# ltc2344-16.net
KiCad netlist of a schematic drawn in EAGLE
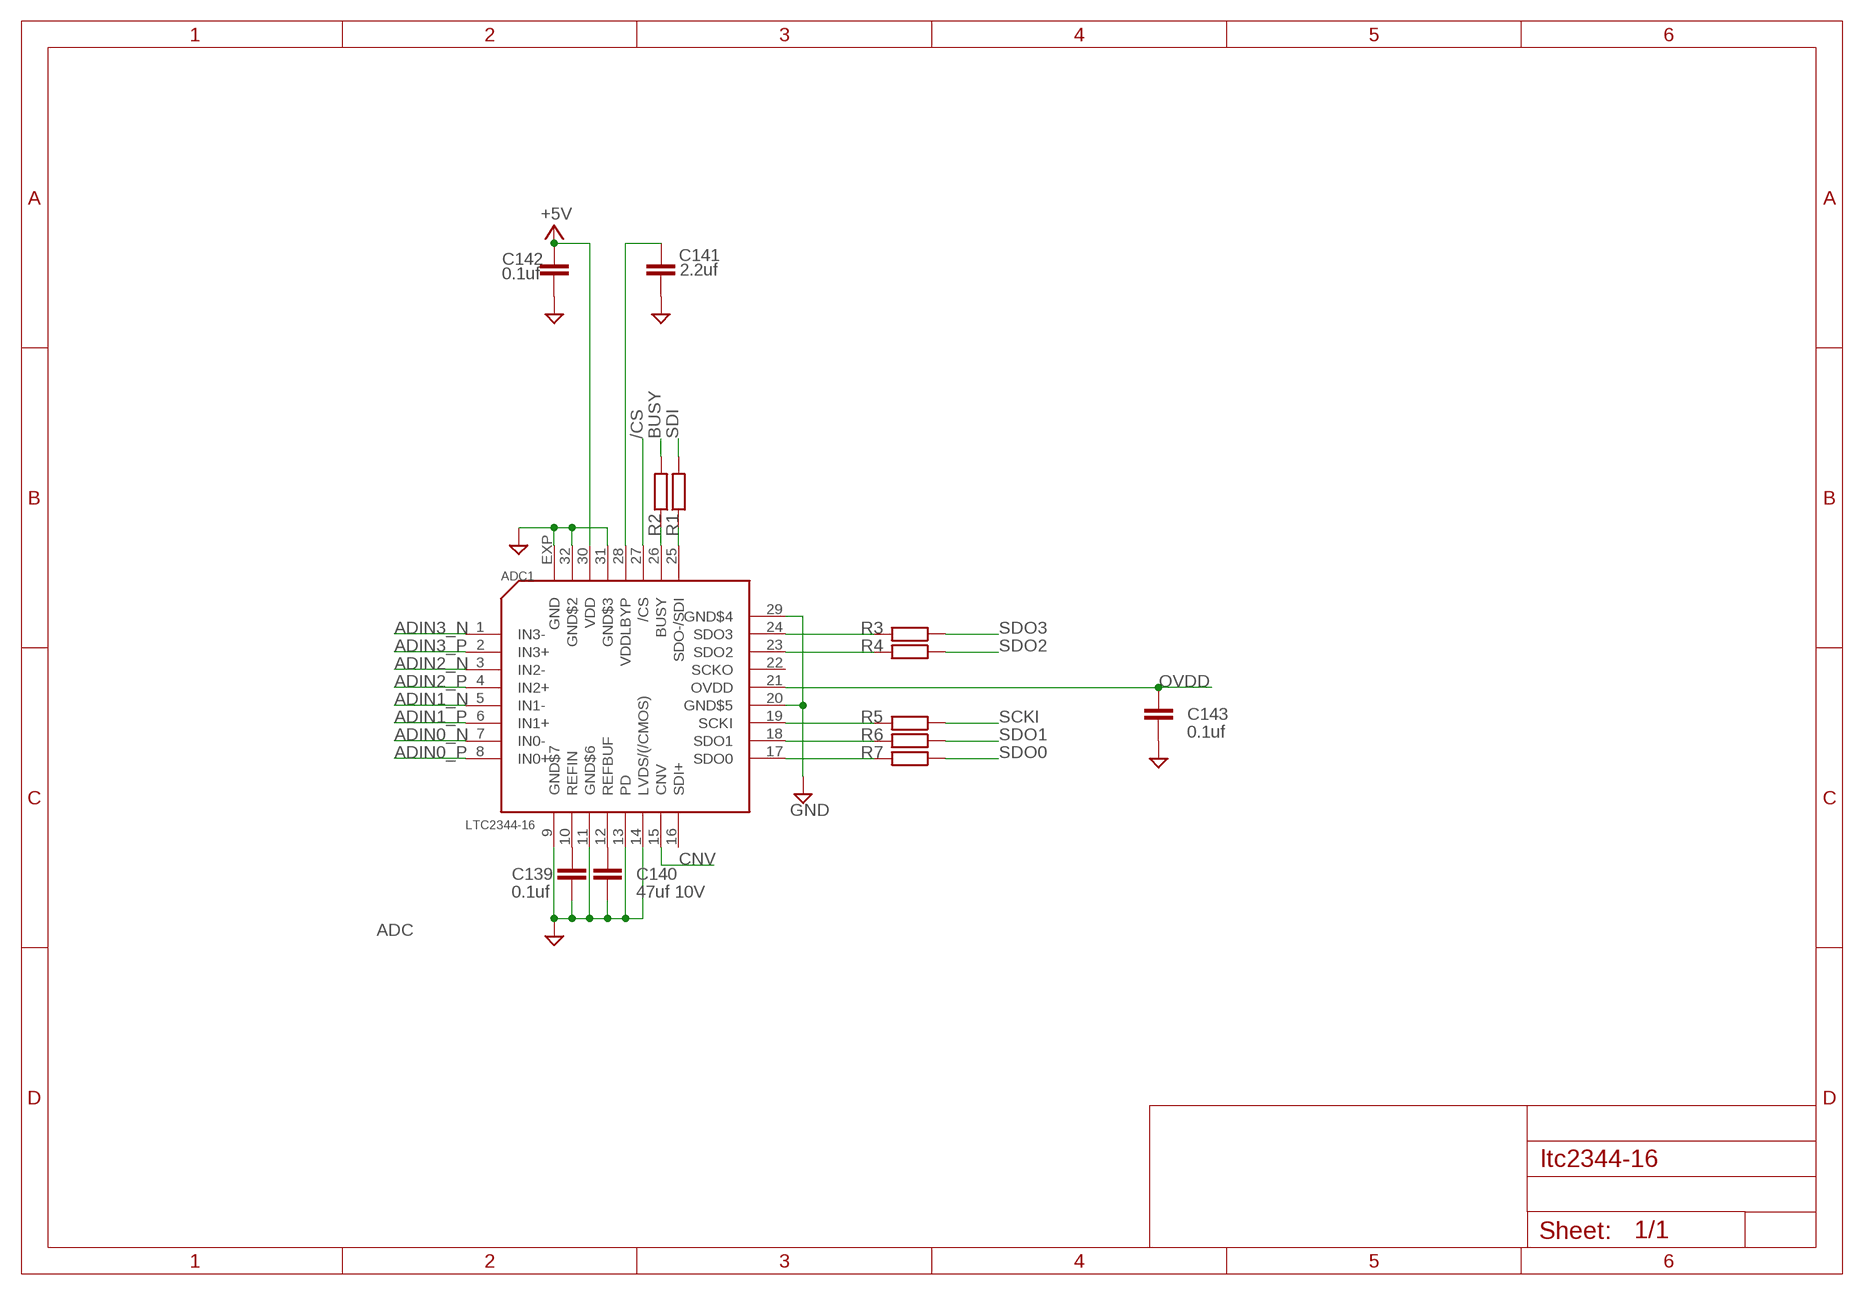
[diagram p0: schematic, sheet 1]

(export (version "E")
  (design (tool "Eeschema 10.0.6"))
  (components
    (comp (ref "ADC1")
      (value "LTC2344-16")
      (footprint "eagle-import:QFN32")
      (libsource (lib "eagle-import") (part "LTC2344-16"))
    )
    (comp (ref "C139")
      (value "0.1uf")
      (footprint "eagle-import:C0402")
      (libsource (lib "eagle-import") (part "C-EUC0402"))
    )
    (comp (ref "C140")
      (value "47uf 10V")
      (footprint "eagle-import:C1210")
      (libsource (lib "eagle-import") (part "C-EUC1210"))
    )
    (comp (ref "C141")
      (value "2.2uf")
      (footprint "eagle-import:C0402")
      (libsource (lib "eagle-import") (part "C-EUC0402"))
    )
    (comp (ref "C142")
      (value "0.1uf")
      (footprint "eagle-import:C0402")
      (libsource (lib "eagle-import") (part "C-EUC0402"))
    )
    (comp (ref "C143")
      (value "0.1uf")
      (footprint "eagle-import:C0402")
      (libsource (lib "eagle-import") (part "C-EUC0402"))
    )
    (comp (ref "R1")
      (value "33R")
      (footprint "eagle-import:R0402")
      (libsource (lib "eagle-import") (part "R-EU_R0402"))
    )
    (comp (ref "R2")
      (value "33R")
      (footprint "eagle-import:R0402")
      (libsource (lib "eagle-import") (part "R-EU_R0402"))
    )
    (comp (ref "R3")
      (value "33R")
      (footprint "eagle-import:R0402")
      (libsource (lib "eagle-import") (part "R-EU_R0402"))
    )
    (comp (ref "R4")
      (value "33R")
      (footprint "eagle-import:R0402")
      (libsource (lib "eagle-import") (part "R-EU_R0402"))
    )
    (comp (ref "R5")
      (value "33R")
      (footprint "eagle-import:R0402")
      (libsource (lib "eagle-import") (part "R-EU_R0402"))
    )
    (comp (ref "R6")
      (value "33R")
      (footprint "eagle-import:R0402")
      (libsource (lib "eagle-import") (part "R-EU_R0402"))
    )
    (comp (ref "R7")
      (value "33R")
      (footprint "eagle-import:R0402")
      (libsource (lib "eagle-import") (part "R-EU_R0402"))
    )
  )
  (nets
    (net (code "1") (name "+5V") (class "Default")
      (node (ref "ADC1") (pin "30") (pinfunction "VDD_30") (pintype "bidirectional"))
      (node (ref "C142") (pin "1") (pinfunction "1_1") (pintype "passive"))
    )
    (net (code "2") (name "/ADIN0_N") (class "Default")
      (node (ref "ADC1") (pin "7") (pinfunction "IN0-_7") (pintype "bidirectional"))
    )
    (net (code "3") (name "/ADIN0_P") (class "Default")
      (node (ref "ADC1") (pin "8") (pinfunction "IN0+_8") (pintype "bidirectional"))
    )
    (net (code "4") (name "/ADIN1_N") (class "Default")
      (node (ref "ADC1") (pin "5") (pinfunction "IN1-_5") (pintype "bidirectional"))
    )
    (net (code "5") (name "/ADIN1_P") (class "Default")
      (node (ref "ADC1") (pin "6") (pinfunction "IN1+_6") (pintype "bidirectional"))
    )
    (net (code "6") (name "/ADIN2_N") (class "Default")
      (node (ref "ADC1") (pin "3") (pinfunction "IN2-_3") (pintype "bidirectional"))
    )
    (net (code "7") (name "/ADIN2_P") (class "Default")
      (node (ref "ADC1") (pin "4") (pinfunction "IN2+_4") (pintype "bidirectional"))
    )
    (net (code "8") (name "/ADIN3_N") (class "Default")
      (node (ref "ADC1") (pin "1") (pinfunction "IN3-_1") (pintype "bidirectional"))
    )
    (net (code "9") (name "/ADIN3_P") (class "Default")
      (node (ref "ADC1") (pin "2") (pinfunction "IN3+_2") (pintype "bidirectional"))
    )
    (net (code "10") (name "/BUSY") (class "Default")
      (node (ref "R2") (pin "2") (pinfunction "2_2") (pintype "passive"))
    )
    (net (code "11") (name "/CNV") (class "Default")
      (node (ref "ADC1") (pin "15") (pinfunction "CNV_15") (pintype "bidirectional"))
    )
    (net (code "12") (name "/OVDD") (class "Default")
      (node (ref "ADC1") (pin "21") (pinfunction "OVDD_21") (pintype "bidirectional"))
      (node (ref "C143") (pin "1") (pinfunction "1_1") (pintype "passive"))
    )
    (net (code "13") (name "/SCKI") (class "Default")
      (node (ref "R5") (pin "1") (pinfunction "1_1") (pintype "passive"))
    )
    (net (code "14") (name "/SDI") (class "Default")
      (node (ref "R1") (pin "2") (pinfunction "2_2") (pintype "passive"))
    )
    (net (code "15") (name "/SDO0") (class "Default")
      (node (ref "R7") (pin "1") (pinfunction "1_1") (pintype "passive"))
    )
    (net (code "16") (name "/SDO1") (class "Default")
      (node (ref "R6") (pin "1") (pinfunction "1_1") (pintype "passive"))
    )
    (net (code "17") (name "/SDO2") (class "Default")
      (node (ref "R4") (pin "1") (pinfunction "1_1") (pintype "passive"))
    )
    (net (code "18") (name "/SDO3") (class "Default")
      (node (ref "R3") (pin "1") (pinfunction "1_1") (pintype "passive"))
    )
    (net (code "19") (name "/{slash}CS") (class "Default")
      (node (ref "ADC1") (pin "27") (pinfunction "/CS_27") (pintype "bidirectional"))
    )
    (net (code "20") (name "GND") (class "Default")
      (node (ref "ADC1") (pin "11") (pinfunction "GND$6_11") (pintype "bidirectional"))
      (node (ref "ADC1") (pin "13") (pinfunction "PD_13") (pintype "bidirectional"))
      (node (ref "ADC1") (pin "14") (pinfunction "LVDS/(/CMOS)_14") (pintype "bidirectional"))
      (node (ref "ADC1") (pin "20") (pinfunction "GND$5_20") (pintype "bidirectional"))
      (node (ref "ADC1") (pin "29") (pinfunction "GND$4_29") (pintype "bidirectional"))
      (node (ref "ADC1") (pin "31") (pinfunction "GND$3_31") (pintype "bidirectional"))
      (node (ref "ADC1") (pin "32") (pinfunction "GND$2_32") (pintype "bidirectional"))
      (node (ref "ADC1") (pin "9") (pinfunction "GND$7_9") (pintype "bidirectional"))
      (node (ref "ADC1") (pin "EXP") (pinfunction "GND_EXP") (pintype "bidirectional"))
      (node (ref "C139") (pin "2") (pinfunction "2_2") (pintype "passive"))
      (node (ref "C140") (pin "2") (pinfunction "2_2") (pintype "passive"))
      (node (ref "C141") (pin "2") (pinfunction "2_2") (pintype "passive"))
      (node (ref "C142") (pin "2") (pinfunction "2_2") (pintype "passive"))
      (node (ref "C143") (pin "2") (pinfunction "2_2") (pintype "passive"))
    )
    (net (code "21") (name "Net-(ADC1-BUSY)") (class "Default")
      (node (ref "ADC1") (pin "26") (pinfunction "BUSY_26") (pintype "bidirectional"))
      (node (ref "R2") (pin "1") (pinfunction "1_1") (pintype "passive"))
    )
    (net (code "22") (name "Net-(ADC1-REFBUF)") (class "Default")
      (node (ref "ADC1") (pin "12") (pinfunction "REFBUF_12") (pintype "bidirectional"))
      (node (ref "C140") (pin "1") (pinfunction "1_1") (pintype "passive"))
    )
    (net (code "23") (name "Net-(ADC1-REFIN)") (class "Default")
      (node (ref "ADC1") (pin "10") (pinfunction "REFIN_10") (pintype "bidirectional"))
      (node (ref "C139") (pin "1") (pinfunction "1_1") (pintype "passive"))
    )
    (net (code "24") (name "Net-(ADC1-SCKI)") (class "Default")
      (node (ref "ADC1") (pin "19") (pinfunction "SCKI_19") (pintype "bidirectional"))
      (node (ref "R5") (pin "2") (pinfunction "2_2") (pintype "passive"))
    )
    (net (code "25") (name "Net-(ADC1-SDO-{slash}SDI)") (class "Default")
      (node (ref "ADC1") (pin "25") (pinfunction "SDO-/SDI_25") (pintype "bidirectional"))
      (node (ref "R1") (pin "1") (pinfunction "1_1") (pintype "passive"))
    )
    (net (code "26") (name "Net-(ADC1-SDO0)") (class "Default")
      (node (ref "ADC1") (pin "17") (pinfunction "SDO0_17") (pintype "bidirectional"))
      (node (ref "R7") (pin "2") (pinfunction "2_2") (pintype "passive"))
    )
    (net (code "27") (name "Net-(ADC1-SDO1)") (class "Default")
      (node (ref "ADC1") (pin "18") (pinfunction "SDO1_18") (pintype "bidirectional"))
      (node (ref "R6") (pin "2") (pinfunction "2_2") (pintype "passive"))
    )
    (net (code "28") (name "Net-(ADC1-SDO2)") (class "Default")
      (node (ref "ADC1") (pin "23") (pinfunction "SDO2_23") (pintype "bidirectional"))
      (node (ref "R4") (pin "2") (pinfunction "2_2") (pintype "passive"))
    )
    (net (code "29") (name "Net-(ADC1-SDO3)") (class "Default")
      (node (ref "ADC1") (pin "24") (pinfunction "SDO3_24") (pintype "bidirectional"))
      (node (ref "R3") (pin "2") (pinfunction "2_2") (pintype "passive"))
    )
    (net (code "30") (name "Net-(ADC1-VDDLBYP)") (class "Default")
      (node (ref "ADC1") (pin "28") (pinfunction "VDDLBYP_28") (pintype "bidirectional"))
      (node (ref "C141") (pin "1") (pinfunction "1_1") (pintype "passive"))
    )
    (net (code "31") (name "unconnected-(ADC1-SCKO-Pad22)") (class "Default")
      (node (ref "ADC1") (pin "22") (pinfunction "SCKO_22") (pintype "bidirectional"))
    )
    (net (code "32") (name "unconnected-(ADC1-SDI+-Pad16)") (class "Default")
      (node (ref "ADC1") (pin "16") (pinfunction "SDI+_16") (pintype "bidirectional"))
    )
  )
)
